# PLD_Local-Supply.net
KiCad netlist of a schematic drawn in Altium Designer
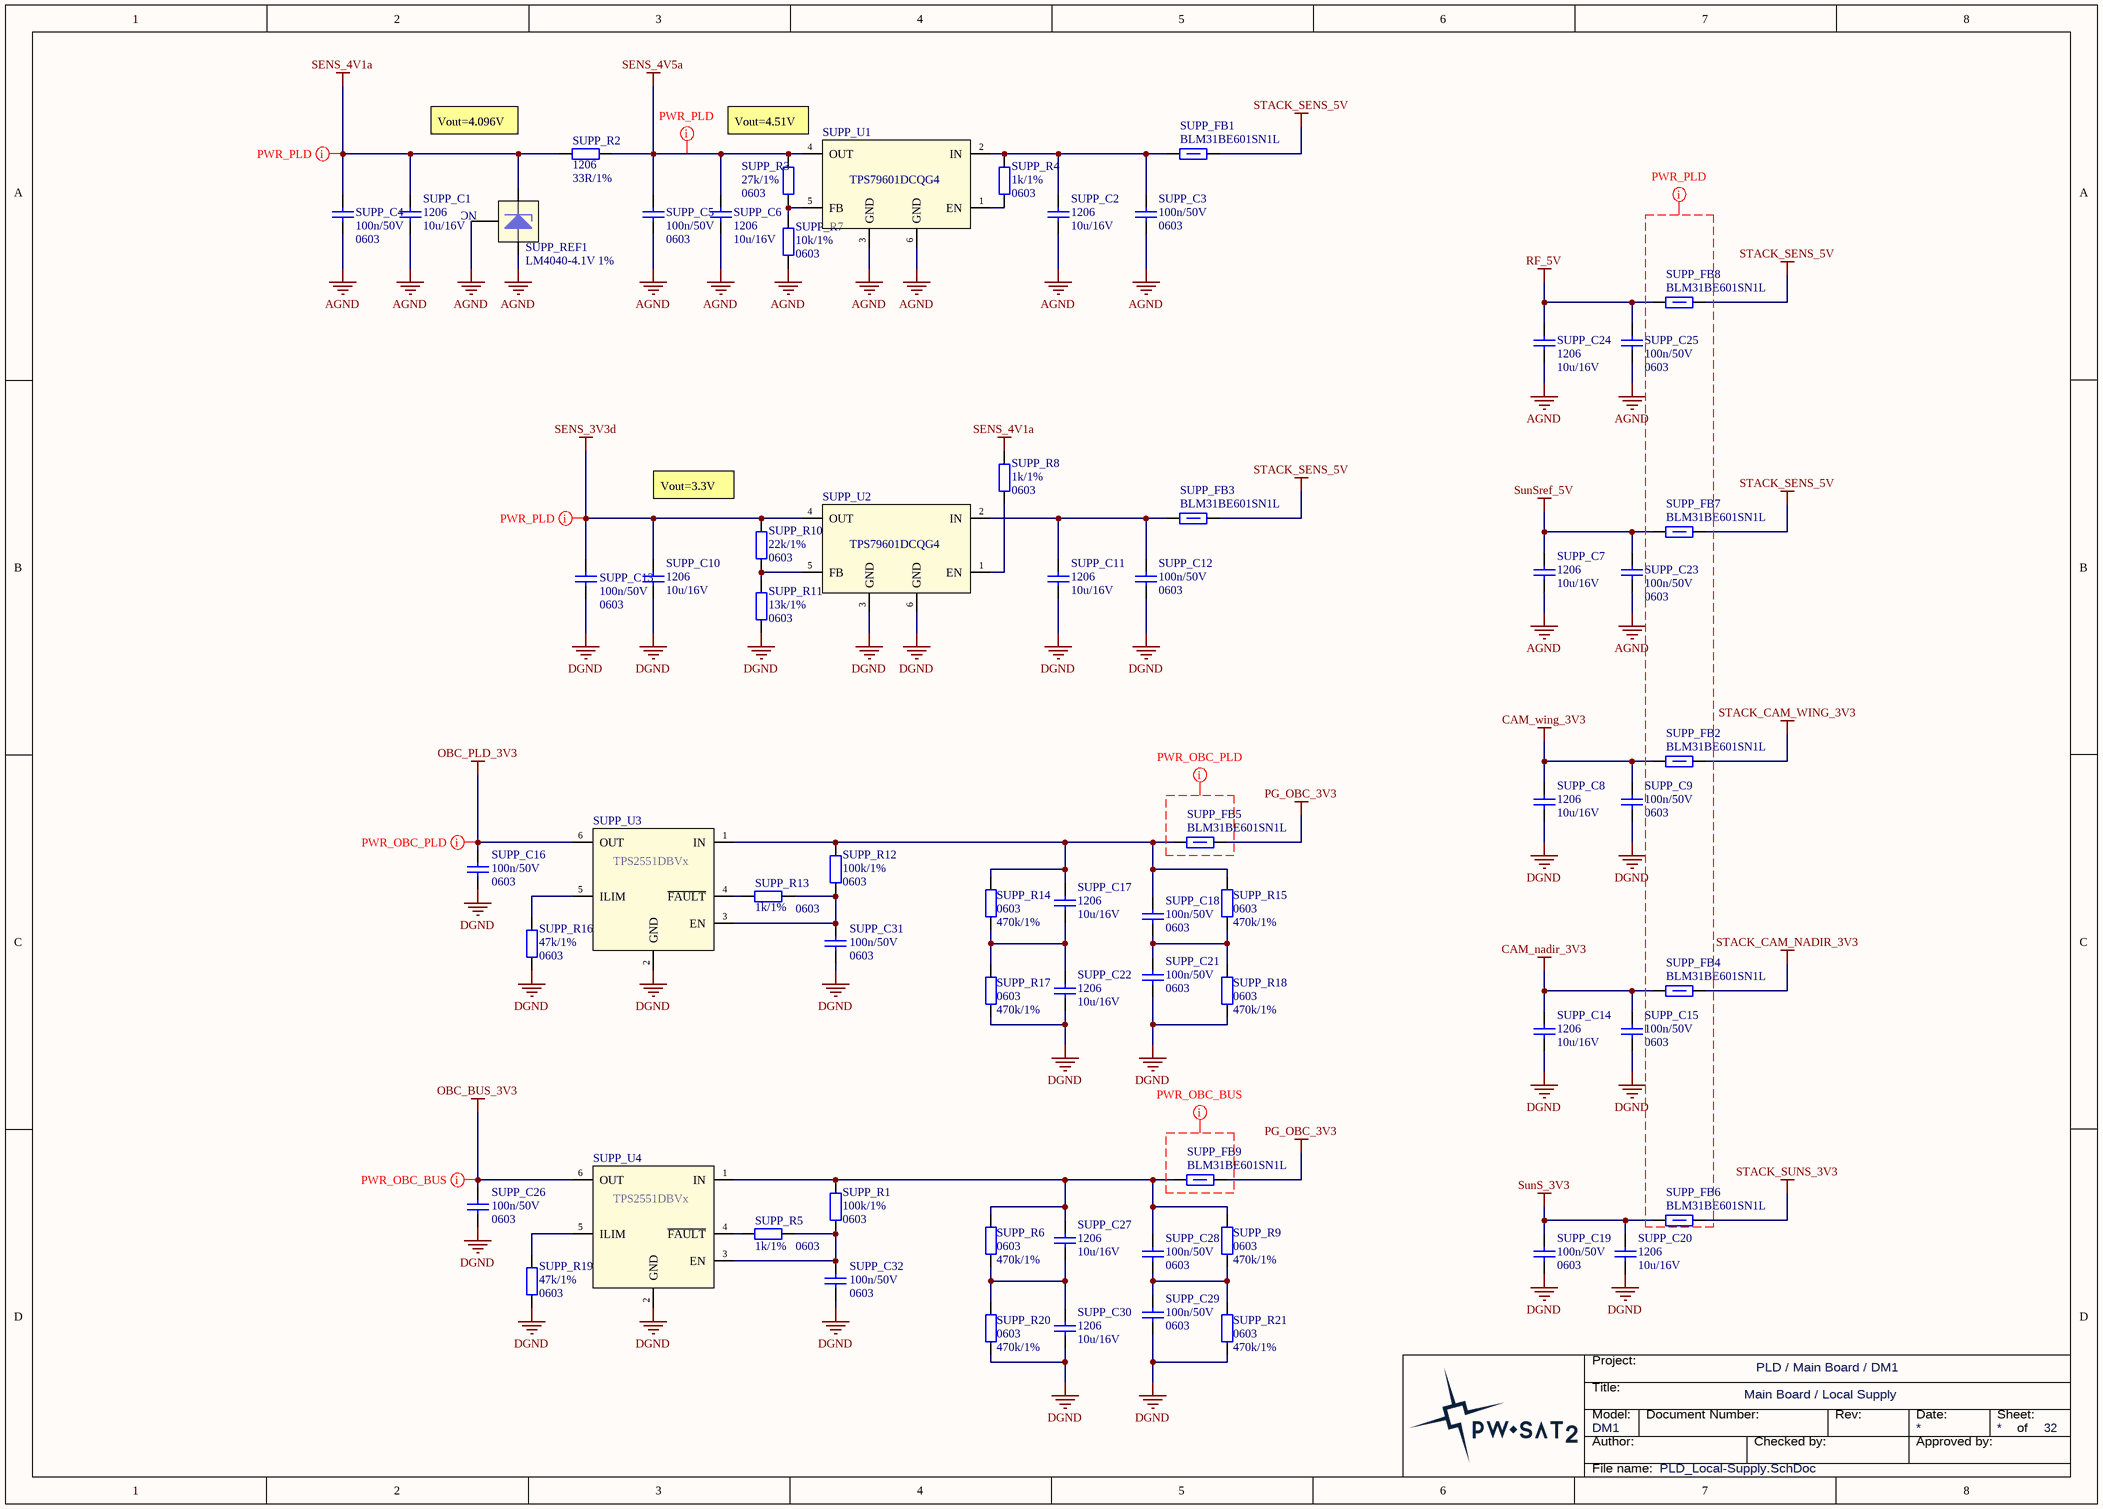
[diagram p0: PLD_Local-Supply.SchDoc]

(export (version "E")
  (design (tool "Eeschema 10.0.6"))
  (components
    (comp (ref "SUPP_C1")
      (value "10u/16V")
      (footprint "SMD_Capacitor_1206")
      (description "Ceramic Cap Kemet COTS 10u/16V X7R 1206")
      (fields
        (field (name "MANUFACTURERPARTNUMBER") "C1206T106K4RACTU")
        (field (name "MANUFACTURER") "Kemet")
        (field (name "PACKGE") "1206")
      )
      (libsource (lib "capacitors") (part "Cer_C1206T106K4RACTU"))
    )
    (comp (ref "SUPP_C2")
      (value "10u/16V")
      (footprint "SMD_Capacitor_1206")
      (description "Ceramic Cap Kemet COTS 10u/16V X7R 1206")
      (fields
        (field (name "MANUFACTURERPARTNUMBER") "C1206T106K4RACTU")
        (field (name "MANUFACTURER") "Kemet")
        (field (name "PACKGE") "1206")
      )
      (libsource (lib "capacitors") (part "Cer_C1206T106K4RACTU"))
    )
    (comp (ref "SUPP_C3")
      (value "100n/50V")
      (footprint "SMD_Capacitor_0603")
      (description "Ceramic Cap Kemet COTS 100n/50V X7R 0603")
      (fields
        (field (name "MANUFACTURER") "Kemet")
        (field (name "MANUFACTURERPARTNUMBER") "C0603T104K5RALTU")
        (field (name "PACKAGE") "0603")
      )
      (libsource (lib "capacitors") (part "Cer_C0603T104K5RALTU"))
    )
    (comp (ref "SUPP_C4")
      (value "100n/50V")
      (footprint "SMD_Capacitor_0603")
      (description "Ceramic Cap Kemet COTS 100n/50V X7R 0603")
      (fields
        (field (name "MANUFACTURER") "Kemet")
        (field (name "MANUFACTURERPARTNUMBER") "C0603T104K5RALTU")
        (field (name "PACKAGE") "0603")
      )
      (libsource (lib "capacitors") (part "Cer_C0603T104K5RALTU"))
    )
    (comp (ref "SUPP_C5")
      (value "100n/50V")
      (footprint "SMD_Capacitor_0603")
      (description "Ceramic Cap Kemet COTS 100n/50V X7R 0603")
      (fields
        (field (name "MANUFACTURER") "Kemet")
        (field (name "MANUFACTURERPARTNUMBER") "C0603T104K5RALTU")
        (field (name "PACKAGE") "0603")
      )
      (libsource (lib "capacitors") (part "Cer_C0603T104K5RALTU"))
    )
    (comp (ref "SUPP_C6")
      (value "10u/16V")
      (footprint "SMD_Capacitor_1206")
      (description "Ceramic Cap Kemet COTS 10u/16V X7R 1206")
      (fields
        (field (name "MANUFACTURERPARTNUMBER") "C1206T106K4RACTU")
        (field (name "MANUFACTURER") "Kemet")
        (field (name "PACKGE") "1206")
      )
      (libsource (lib "capacitors") (part "Cer_C1206T106K4RACTU"))
    )
    (comp (ref "SUPP_C7")
      (value "10u/16V")
      (footprint "SMD_Capacitor_1206")
      (description "Ceramic Cap Kemet COTS 10u/16V X7R 1206")
      (fields
        (field (name "MANUFACTURERPARTNUMBER") "C1206T106K4RACTU")
        (field (name "MANUFACTURER") "Kemet")
        (field (name "PACKGE") "1206")
      )
      (libsource (lib "capacitors") (part "Cer_C1206T106K4RACTU"))
    )
    (comp (ref "SUPP_C8")
      (value "10u/16V")
      (footprint "SMD_Capacitor_1206")
      (description "Ceramic Cap Kemet COTS 10u/16V X7R 1206")
      (fields
        (field (name "MANUFACTURERPARTNUMBER") "C1206T106K4RACTU")
        (field (name "MANUFACTURER") "Kemet")
        (field (name "PACKGE") "1206")
      )
      (libsource (lib "capacitors") (part "Cer_C1206T106K4RACTU"))
    )
    (comp (ref "SUPP_C9")
      (value "100n/50V")
      (footprint "SMD_Capacitor_0603")
      (description "Ceramic Cap Kemet COTS 100n/50V X7R 0603")
      (fields
        (field (name "MANUFACTURER") "Kemet")
        (field (name "MANUFACTURERPARTNUMBER") "C0603T104K5RALTU")
        (field (name "PACKAGE") "0603")
      )
      (libsource (lib "capacitors") (part "Cer_C0603T104K5RALTU"))
    )
    (comp (ref "SUPP_C10")
      (value "10u/16V")
      (footprint "SMD_Capacitor_1206")
      (description "Ceramic Cap Kemet COTS 10u/16V X7R 1206")
      (fields
        (field (name "MANUFACTURERPARTNUMBER") "C1206T106K4RACTU")
        (field (name "MANUFACTURER") "Kemet")
        (field (name "PACKGE") "1206")
      )
      (libsource (lib "capacitors") (part "Cer_C1206T106K4RACTU"))
    )
    (comp (ref "SUPP_C11")
      (value "10u/16V")
      (footprint "SMD_Capacitor_1206")
      (description "Ceramic Cap Kemet COTS 10u/16V X7R 1206")
      (fields
        (field (name "MANUFACTURERPARTNUMBER") "C1206T106K4RACTU")
        (field (name "MANUFACTURER") "Kemet")
        (field (name "PACKGE") "1206")
      )
      (libsource (lib "capacitors") (part "Cer_C1206T106K4RACTU"))
    )
    (comp (ref "SUPP_C12")
      (value "100n/50V")
      (footprint "SMD_Capacitor_0603")
      (description "Ceramic Cap Kemet COTS 100n/50V X7R 0603")
      (fields
        (field (name "MANUFACTURER") "Kemet")
        (field (name "MANUFACTURERPARTNUMBER") "C0603T104K5RALTU")
        (field (name "PACKAGE") "0603")
      )
      (libsource (lib "capacitors") (part "Cer_C0603T104K5RALTU"))
    )
    (comp (ref "SUPP_C13")
      (value "100n/50V")
      (footprint "SMD_Capacitor_0603")
      (description "Ceramic Cap Kemet COTS 100n/50V X7R 0603")
      (fields
        (field (name "MANUFACTURER") "Kemet")
        (field (name "MANUFACTURERPARTNUMBER") "C0603T104K5RALTU")
        (field (name "PACKAGE") "0603")
      )
      (libsource (lib "capacitors") (part "Cer_C0603T104K5RALTU"))
    )
    (comp (ref "SUPP_C14")
      (value "10u/16V")
      (footprint "SMD_Capacitor_1206")
      (description "Ceramic Cap Kemet COTS 10u/16V X7R 1206")
      (fields
        (field (name "MANUFACTURERPARTNUMBER") "C1206T106K4RACTU")
        (field (name "MANUFACTURER") "Kemet")
        (field (name "PACKGE") "1206")
      )
      (libsource (lib "capacitors") (part "Cer_C1206T106K4RACTU"))
    )
    (comp (ref "SUPP_C15")
      (value "100n/50V")
      (footprint "SMD_Capacitor_0603")
      (description "Ceramic Cap Kemet COTS 100n/50V X7R 0603")
      (fields
        (field (name "MANUFACTURER") "Kemet")
        (field (name "MANUFACTURERPARTNUMBER") "C0603T104K5RALTU")
        (field (name "PACKAGE") "0603")
      )
      (libsource (lib "capacitors") (part "Cer_C0603T104K5RALTU"))
    )
    (comp (ref "SUPP_C16")
      (value "100n/50V")
      (footprint "SMD_Capacitor_0603")
      (description "Ceramic Cap Kemet COTS 100n/50V X7R 0603")
      (fields
        (field (name "MANUFACTURER") "Kemet")
        (field (name "MANUFACTURERPARTNUMBER") "C0603T104K5RALTU")
        (field (name "PACKAGE") "0603")
      )
      (libsource (lib "capacitors") (part "Cer_C0603T104K5RALTU"))
    )
    (comp (ref "SUPP_C17")
      (value "10u/16V")
      (footprint "SMD_Capacitor_1206")
      (description "Ceramic Cap Kemet COTS 10u/16V X7R 1206")
      (fields
        (field (name "MANUFACTURERPARTNUMBER") "C1206T106K4RACTU")
        (field (name "MANUFACTURER") "Kemet")
        (field (name "PACKGE") "1206")
      )
      (libsource (lib "capacitors") (part "Cer_C1206T106K4RACTU"))
    )
    (comp (ref "SUPP_C18")
      (value "100n/50V")
      (footprint "SMD_Capacitor_0603")
      (description "Ceramic Cap Kemet COTS 100n/50V X7R 0603")
      (fields
        (field (name "MANUFACTURER") "Kemet")
        (field (name "MANUFACTURERPARTNUMBER") "C0603T104K5RALTU")
        (field (name "PACKAGE") "0603")
      )
      (libsource (lib "capacitors") (part "Cer_C0603T104K5RALTU"))
    )
    (comp (ref "SUPP_C19")
      (value "100n/50V")
      (footprint "SMD_Capacitor_0603")
      (description "Ceramic Cap Kemet COTS 100n/50V X7R 0603")
      (fields
        (field (name "MANUFACTURER") "Kemet")
        (field (name "MANUFACTURERPARTNUMBER") "C0603T104K5RALTU")
        (field (name "PACKAGE") "0603")
      )
      (libsource (lib "capacitors") (part "Cer_C0603T104K5RALTU"))
    )
    (comp (ref "SUPP_C20")
      (value "10u/16V")
      (footprint "SMD_Capacitor_1206")
      (description "Ceramic Cap Kemet COTS 10u/16V X7R 1206")
      (fields
        (field (name "MANUFACTURERPARTNUMBER") "C1206T106K4RACTU")
        (field (name "MANUFACTURER") "Kemet")
        (field (name "PACKGE") "1206")
      )
      (libsource (lib "capacitors") (part "Cer_C1206T106K4RACTU"))
    )
    (comp (ref "SUPP_C21")
      (value "100n/50V")
      (footprint "SMD_Capacitor_0603")
      (description "Ceramic Cap Kemet COTS 100n/50V X7R 0603")
      (fields
        (field (name "MANUFACTURER") "Kemet")
        (field (name "MANUFACTURERPARTNUMBER") "C0603T104K5RALTU")
        (field (name "PACKAGE") "0603")
      )
      (libsource (lib "capacitors") (part "Cer_C0603T104K5RALTU"))
    )
    (comp (ref "SUPP_C22")
      (value "10u/16V")
      (footprint "SMD_Capacitor_1206")
      (description "Ceramic Cap Kemet COTS 10u/16V X7R 1206")
      (fields
        (field (name "MANUFACTURERPARTNUMBER") "C1206T106K4RACTU")
        (field (name "MANUFACTURER") "Kemet")
        (field (name "PACKGE") "1206")
      )
      (libsource (lib "capacitors") (part "Cer_C1206T106K4RACTU"))
    )
    (comp (ref "SUPP_C23")
      (value "100n/50V")
      (footprint "SMD_Capacitor_0603")
      (description "Ceramic Cap Kemet COTS 100n/50V X7R 0603")
      (fields
        (field (name "MANUFACTURER") "Kemet")
        (field (name "MANUFACTURERPARTNUMBER") "C0603T104K5RALTU")
        (field (name "PACKAGE") "0603")
      )
      (libsource (lib "capacitors") (part "Cer_C0603T104K5RALTU"))
    )
    (comp (ref "SUPP_C24")
      (value "10u/16V")
      (footprint "SMD_Capacitor_1206")
      (description "Ceramic Cap Kemet COTS 10u/16V X7R 1206")
      (fields
        (field (name "MANUFACTURERPARTNUMBER") "C1206T106K4RACTU")
        (field (name "MANUFACTURER") "Kemet")
        (field (name "PACKGE") "1206")
      )
      (libsource (lib "capacitors") (part "Cer_C1206T106K4RACTU"))
    )
    (comp (ref "SUPP_C25")
      (value "100n/50V")
      (footprint "SMD_Capacitor_0603")
      (description "Ceramic Cap Kemet COTS 100n/50V X7R 0603")
      (fields
        (field (name "MANUFACTURER") "Kemet")
        (field (name "MANUFACTURERPARTNUMBER") "C0603T104K5RALTU")
        (field (name "PACKAGE") "0603")
      )
      (libsource (lib "capacitors") (part "Cer_C0603T104K5RALTU"))
    )
    (comp (ref "SUPP_C26")
      (value "100n/50V")
      (footprint "SMD_Capacitor_0603")
      (description "Ceramic Cap Kemet COTS 100n/50V X7R 0603")
      (fields
        (field (name "MANUFACTURER") "Kemet")
        (field (name "MANUFACTURERPARTNUMBER") "C0603T104K5RALTU")
        (field (name "PACKAGE") "0603")
      )
      (libsource (lib "capacitors") (part "Cer_C0603T104K5RALTU"))
    )
    (comp (ref "SUPP_C27")
      (value "10u/16V")
      (footprint "SMD_Capacitor_1206")
      (description "Ceramic Cap Kemet COTS 10u/16V X7R 1206")
      (fields
        (field (name "MANUFACTURERPARTNUMBER") "C1206T106K4RACTU")
        (field (name "MANUFACTURER") "Kemet")
        (field (name "PACKGE") "1206")
      )
      (libsource (lib "capacitors") (part "Cer_C1206T106K4RACTU"))
    )
    (comp (ref "SUPP_C28")
      (value "100n/50V")
      (footprint "SMD_Capacitor_0603")
      (description "Ceramic Cap Kemet COTS 100n/50V X7R 0603")
      (fields
        (field (name "MANUFACTURER") "Kemet")
        (field (name "MANUFACTURERPARTNUMBER") "C0603T104K5RALTU")
        (field (name "PACKAGE") "0603")
      )
      (libsource (lib "capacitors") (part "Cer_C0603T104K5RALTU"))
    )
    (comp (ref "SUPP_C29")
      (value "100n/50V")
      (footprint "SMD_Capacitor_0603")
      (description "Ceramic Cap Kemet COTS 100n/50V X7R 0603")
      (fields
        (field (name "MANUFACTURER") "Kemet")
        (field (name "MANUFACTURERPARTNUMBER") "C0603T104K5RALTU")
        (field (name "PACKAGE") "0603")
      )
      (libsource (lib "capacitors") (part "Cer_C0603T104K5RALTU"))
    )
    (comp (ref "SUPP_C30")
      (value "10u/16V")
      (footprint "SMD_Capacitor_1206")
      (description "Ceramic Cap Kemet COTS 10u/16V X7R 1206")
      (fields
        (field (name "MANUFACTURERPARTNUMBER") "C1206T106K4RACTU")
        (field (name "MANUFACTURER") "Kemet")
        (field (name "PACKGE") "1206")
      )
      (libsource (lib "capacitors") (part "Cer_C1206T106K4RACTU"))
    )
    (comp (ref "SUPP_C31")
      (value "100n/50V")
      (footprint "SMD_Capacitor_0603")
      (description "Ceramic Cap Kemet COTS 100n/50V X7R 0603")
      (fields
        (field (name "MANUFACTURER") "Kemet")
        (field (name "MANUFACTURERPARTNUMBER") "C0603T104K5RALTU")
        (field (name "PACKAGE") "0603")
      )
      (libsource (lib "capacitors") (part "Cer_C0603T104K5RALTU"))
    )
    (comp (ref "SUPP_C32")
      (value "100n/50V")
      (footprint "SMD_Capacitor_0603")
      (description "Ceramic Cap Kemet COTS 100n/50V X7R 0603")
      (fields
        (field (name "MANUFACTURER") "Kemet")
        (field (name "MANUFACTURERPARTNUMBER") "C0603T104K5RALTU")
        (field (name "PACKAGE") "0603")
      )
      (libsource (lib "capacitors") (part "Cer_C0603T104K5RALTU"))
    )
    (comp (ref "SUPP_FB1")
      (value "600R/100MHz")
      (footprint "1206")
      (description "Ferrite Bead")
      (fields (field (name "MANUFACTURER") "Murata") (field (name "MANUFACTURERPARTNUMBER") "BLM31BE601SN1L"))
      (libsource (lib "inductors") (part "FerriteBead"))
    )
    (comp (ref "SUPP_FB2")
      (value "600R/100MHz")
      (footprint "1206")
      (description "Ferrite Bead")
      (fields (field (name "MANUFACTURER") "Murata") (field (name "MANUFACTURERPARTNUMBER") "BLM31BE601SN1L"))
      (libsource (lib "inductors") (part "FerriteBead"))
    )
    (comp (ref "SUPP_FB3")
      (value "600R/100MHz")
      (footprint "1206")
      (description "Ferrite Bead")
      (fields (field (name "MANUFACTURER") "Murata") (field (name "MANUFACTURERPARTNUMBER") "BLM31BE601SN1L"))
      (libsource (lib "inductors") (part "FerriteBead"))
    )
    (comp (ref "SUPP_FB4")
      (value "600R/100MHz")
      (footprint "1206")
      (description "Ferrite Bead")
      (fields (field (name "MANUFACTURER") "Murata") (field (name "MANUFACTURERPARTNUMBER") "BLM31BE601SN1L"))
      (libsource (lib "inductors") (part "FerriteBead"))
    )
    (comp (ref "SUPP_FB5")
      (value "600R/100MHz")
      (footprint "1206")
      (description "Ferrite Bead")
      (fields (field (name "MANUFACTURER") "Murata") (field (name "MANUFACTURERPARTNUMBER") "BLM31BE601SN1L"))
      (libsource (lib "inductors") (part "FerriteBead"))
    )
    (comp (ref "SUPP_FB6")
      (value "600R/100MHz")
      (footprint "1206")
      (description "Ferrite Bead")
      (fields (field (name "MANUFACTURER") "Murata") (field (name "MANUFACTURERPARTNUMBER") "BLM31BE601SN1L"))
      (libsource (lib "inductors") (part "FerriteBead"))
    )
    (comp (ref "SUPP_FB7")
      (value "600R/100MHz")
      (footprint "1206")
      (description "Ferrite Bead")
      (fields (field (name "MANUFACTURER") "Murata") (field (name "MANUFACTURERPARTNUMBER") "BLM31BE601SN1L"))
      (libsource (lib "inductors") (part "FerriteBead"))
    )
    (comp (ref "SUPP_FB8")
      (value "600R/100MHz")
      (footprint "1206")
      (description "Ferrite Bead")
      (fields (field (name "MANUFACTURER") "Murata") (field (name "MANUFACTURERPARTNUMBER") "BLM31BE601SN1L"))
      (libsource (lib "inductors") (part "FerriteBead"))
    )
    (comp (ref "SUPP_FB9")
      (value "600R/100MHz")
      (footprint "1206")
      (description "Ferrite Bead")
      (fields (field (name "MANUFACTURER") "Murata") (field (name "MANUFACTURERPARTNUMBER") "BLM31BE601SN1L"))
      (libsource (lib "inductors") (part "FerriteBead"))
    )
    (comp (ref "SUPP_R1")
      (value "100k/1%")
      (footprint "SMD_Resistor_0603")
      (description "100k/1% Vishay CRCW 0603 Resistor. 100mW, 100ppm, 75V.")
      (fields
        (field (name "MANUFACTURER") "Vishay")
        (field (name "MANUFACTURERPARTNUMBER") "CRCW0603100KFKxxxx")
        (field (name "PACKAGE") "0603")
      )
      (libsource (lib "resistors") (part "CRCW0603100KFKxxxx"))
    )
    (comp (ref "SUPP_R2")
      (value "33R/1%")
      (footprint "SMD_Resistor_1206")
      (description "33R/1% Vishay CRCW 1206 Resistor. 250mW, 100ppm, 200V.")
      (fields
        (field (name "MANUFACTURERPARTNUMBER") "CRCW120633R0FKxxxx")
        (field (name "MANUFACTURER") "Vishay")
        (field (name "PACKAGE") "1206")
      )
      (libsource (lib "resistors") (part "CRCW120633R0FKxxxx"))
    )
    (comp (ref "SUPP_R3")
      (value "27k/1%")
      (footprint "SMD_Resistor_0603")
      (fields (field (name "PACKAGE") "0603"))
      (libsource (lib "resistors") (part "Res"))
    )
    (comp (ref "SUPP_R4")
      (value "1k/1%")
      (footprint "SMD_Resistor_0603")
      (description "1k/1% Vishay CRCW 0603 Resistor. 100mW, 100ppm, 75V.")
      (fields
        (field (name "MANUFACTURER") "Vishay")
        (field (name "MANUFACTURERPARTNUMBER") "CRCW06031K00FKxxxx")
        (field (name "PACKAGE") "0603")
      )
      (libsource (lib "") (part "CRCW06031K00FKxxxx_1"))
    )
    (comp (ref "SUPP_R5")
      (value "1k/1%")
      (footprint "SMD_Resistor_0603")
      (description "1k/1% Vishay CRCW 0603 Resistor. 100mW, 100ppm, 75V.")
      (fields
        (field (name "MANUFACTURER") "Vishay")
        (field (name "MANUFACTURERPARTNUMBER") "CRCW06031K00FKxxxx")
        (field (name "PACKAGE") "0603")
      )
      (libsource (lib "resistors") (part "CRCW06031K00FKxxxx"))
    )
    (comp (ref "SUPP_R6")
      (value "470k/1%")
      (footprint "SMD_Resistor_0603")
      (description "470k/1% Vishay CRCW 0603 Resistor. 100mW, 100ppm, 75V.")
      (fields
        (field (name "MANUFACTURER") "Vishay")
        (field (name "MANUFACTURERPARTNUMBER") "CRCW0603470KFKxxxx")
        (field (name "PACKAGE") "0603")
      )
      (libsource (lib "") (part "CRCW0603470KFKxxxx_1"))
    )
    (comp (ref "SUPP_R7")
      (value "10k/1%")
      (footprint "SMD_Resistor_0603")
      (description "10k/1% Vishay CRCW 0603 Resistor. 100mW, 100ppm, 75V.")
      (fields
        (field (name "MANUFACTURER") "Vishay")
        (field (name "MANUFACTURERPARTNUMBER") "CRCW060310K0FKxxxx")
        (field (name "PACKAGE") "0603")
      )
      (libsource (lib "resistors") (part "CRCW060310K0FKxxxx"))
    )
    (comp (ref "SUPP_R8")
      (value "1k/1%")
      (footprint "SMD_Resistor_0603")
      (description "1k/1% Vishay CRCW 0603 Resistor. 100mW, 100ppm, 75V.")
      (fields
        (field (name "MANUFACTURER") "Vishay")
        (field (name "MANUFACTURERPARTNUMBER") "CRCW06031K00FKxxxx")
        (field (name "PACKAGE") "0603")
      )
      (libsource (lib "") (part "CRCW06031K00FKxxxx_1"))
    )
    (comp (ref "SUPP_R9")
      (value "470k/1%")
      (footprint "SMD_Resistor_0603")
      (description "470k/1% Vishay CRCW 0603 Resistor. 100mW, 100ppm, 75V.")
      (fields
        (field (name "MANUFACTURER") "Vishay")
        (field (name "MANUFACTURERPARTNUMBER") "CRCW0603470KFKxxxx")
        (field (name "PACKAGE") "0603")
      )
      (libsource (lib "resistors") (part "CRCW0603470KFKxxxx"))
    )
    (comp (ref "SUPP_R10")
      (value "22k/1%")
      (footprint "SMD_Resistor_0603")
      (fields (field (name "PACKAGE") "0603"))
      (libsource (lib "resistors") (part "Res"))
    )
    (comp (ref "SUPP_R11")
      (value "13k/1%")
      (footprint "SMD_Resistor_0603")
      (fields (field (name "PACKAGE") "0603"))
      (libsource (lib "resistors") (part "Res"))
    )
    (comp (ref "SUPP_R12")
      (value "100k/1%")
      (footprint "SMD_Resistor_0603")
      (description "100k/1% Vishay CRCW 0603 Resistor. 100mW, 100ppm, 75V.")
      (fields
        (field (name "MANUFACTURER") "Vishay")
        (field (name "MANUFACTURERPARTNUMBER") "CRCW0603100KFKxxxx")
        (field (name "PACKAGE") "0603")
      )
      (libsource (lib "resistors") (part "CRCW0603100KFKxxxx"))
    )
    (comp (ref "SUPP_R13")
      (value "1k/1%")
      (footprint "SMD_Resistor_0603")
      (description "1k/1% Vishay CRCW 0603 Resistor. 100mW, 100ppm, 75V.")
      (fields
        (field (name "MANUFACTURER") "Vishay")
        (field (name "MANUFACTURERPARTNUMBER") "CRCW06031K00FKxxxx")
        (field (name "PACKAGE") "0603")
      )
      (libsource (lib "resistors") (part "CRCW06031K00FKxxxx"))
    )
    (comp (ref "SUPP_R14")
      (value "470k/1%")
      (footprint "SMD_Resistor_0603")
      (description "470k/1% Vishay CRCW 0603 Resistor. 100mW, 100ppm, 75V.")
      (fields
        (field (name "MANUFACTURER") "Vishay")
        (field (name "MANUFACTURERPARTNUMBER") "CRCW0603470KFKxxxx")
        (field (name "PACKAGE") "0603")
      )
      (libsource (lib "") (part "CRCW0603470KFKxxxx_1"))
    )
    (comp (ref "SUPP_R15")
      (value "470k/1%")
      (footprint "SMD_Resistor_0603")
      (description "470k/1% Vishay CRCW 0603 Resistor. 100mW, 100ppm, 75V.")
      (fields
        (field (name "MANUFACTURER") "Vishay")
        (field (name "MANUFACTURERPARTNUMBER") "CRCW0603470KFKxxxx")
        (field (name "PACKAGE") "0603")
      )
      (libsource (lib "resistors") (part "CRCW0603470KFKxxxx"))
    )
    (comp (ref "SUPP_R16")
      (value "47k/1%")
      (footprint "SMD_Resistor_0603")
      (description "47k/1% Vishay CRCW 0603 Resistor. 100mW, 100ppm, 75V.")
      (fields
        (field (name "MANUFACTURER") "Vishay")
        (field (name "MANUFACTURERPARTNUMBER") "CRCW060347K0FKxxxx")
        (field (name "PACKAGE") "0603")
      )
      (libsource (lib "resistors") (part "CRCW060347K0FKxxxx"))
    )
    (comp (ref "SUPP_R17")
      (value "470k/1%")
      (footprint "SMD_Resistor_0603")
      (description "470k/1% Vishay CRCW 0603 Resistor. 100mW, 100ppm, 75V.")
      (fields
        (field (name "MANUFACTURER") "Vishay")
        (field (name "MANUFACTURERPARTNUMBER") "CRCW0603470KFKxxxx")
        (field (name "PACKAGE") "0603")
      )
      (libsource (lib "") (part "CRCW0603470KFKxxxx_1"))
    )
    (comp (ref "SUPP_R18")
      (value "470k/1%")
      (footprint "SMD_Resistor_0603")
      (description "470k/1% Vishay CRCW 0603 Resistor. 100mW, 100ppm, 75V.")
      (fields
        (field (name "MANUFACTURER") "Vishay")
        (field (name "MANUFACTURERPARTNUMBER") "CRCW0603470KFKxxxx")
        (field (name "PACKAGE") "0603")
      )
      (libsource (lib "resistors") (part "CRCW0603470KFKxxxx"))
    )
    (comp (ref "SUPP_R19")
      (value "47k/1%")
      (footprint "SMD_Resistor_0603")
      (description "47k/1% Vishay CRCW 0603 Resistor. 100mW, 100ppm, 75V.")
      (fields
        (field (name "MANUFACTURER") "Vishay")
        (field (name "MANUFACTURERPARTNUMBER") "CRCW060347K0FKxxxx")
        (field (name "PACKAGE") "0603")
      )
      (libsource (lib "resistors") (part "CRCW060347K0FKxxxx"))
    )
    (comp (ref "SUPP_R20")
      (value "470k/1%")
      (footprint "SMD_Resistor_0603")
      (description "470k/1% Vishay CRCW 0603 Resistor. 100mW, 100ppm, 75V.")
      (fields
        (field (name "MANUFACTURER") "Vishay")
        (field (name "MANUFACTURERPARTNUMBER") "CRCW0603470KFKxxxx")
        (field (name "PACKAGE") "0603")
      )
      (libsource (lib "") (part "CRCW0603470KFKxxxx_1"))
    )
    (comp (ref "SUPP_R21")
      (value "470k/1%")
      (footprint "SMD_Resistor_0603")
      (description "470k/1% Vishay CRCW 0603 Resistor. 100mW, 100ppm, 75V.")
      (fields
        (field (name "MANUFACTURER") "Vishay")
        (field (name "MANUFACTURERPARTNUMBER") "CRCW0603470KFKxxxx")
        (field (name "PACKAGE") "0603")
      )
      (libsource (lib "resistors") (part "CRCW0603470KFKxxxx"))
    )
    (comp (ref "SUPP_REF1")
      (value "LM4040-4.1V 1%")
      (footprint "SOT23-3")
      (description "Shunt V-REF, 4.096V, 1%, SOT23-3")
      (fields
        (field (name "MANUFACTURERPARTNUMBER") "LM4040CIM3-4.1")
        (field (name "MANUFACTURER") "Texas Instruments")
      )
      (libsource (lib "diodes") (part "LM4040CIM3-4.1"))
    )
    (comp (ref "SUPP_U1")
      (value "~")
      (footprint "TI-DCQ")
      (description "1A, Ajdustable LDO, Ultralow-Noise, High PSRR, Fast, RF")
      (fields
        (field (name "MANUFACTURER") "Texas Instruments")
        (field (name "MANUFACTURERPARTNUMBER") "TPS79601DCQG4")
      )
      (libsource (lib "microcircuits") (part "TPS79601DCQG4"))
    )
    (comp (ref "SUPP_U2")
      (value "~")
      (footprint "TI-DCQ")
      (description "1A, Ajdustable LDO, Ultralow-Noise, High PSRR, Fast, RF")
      (fields
        (field (name "MANUFACTURER") "Texas Instruments")
        (field (name "MANUFACTURERPARTNUMBER") "TPS79601DCQG4")
      )
      (libsource (lib "microcircuits") (part "TPS79601DCQG4"))
    )
    (comp (ref "SUPP_U3")
      (value "TPS2551DBVx")
      (footprint "SOT23-6")
      (description "Adjustable Current-Limited Power-Distribution Switch.")
      (fields (field (name "MANUFACTURER") "Texas Instruments"))
      (libsource (lib "microcircuits") (part "TPS2551DBVx"))
    )
    (comp (ref "SUPP_U4")
      (value "TPS2551DBVx")
      (footprint "SOT23-6")
      (description "Adjustable Current-Limited Power-Distribution Switch.")
      (fields (field (name "MANUFACTURER") "Texas Instruments"))
      (libsource (lib "microcircuits") (part "TPS2551DBVx"))
    )
  )
  (nets
    (net (code "1") (name "AGND") (class "Default")
      (node (ref "SUPP_C1") (pin "2") (pinfunction "2_2") (pintype "passive"))
      (node (ref "SUPP_C2") (pin "2") (pinfunction "2_2") (pintype "passive"))
      (node (ref "SUPP_C23") (pin "1") (pinfunction "1_1") (pintype "passive"))
      (node (ref "SUPP_C24") (pin "2") (pinfunction "2_2") (pintype "passive"))
      (node (ref "SUPP_C25") (pin "1") (pinfunction "1_1") (pintype "passive"))
      (node (ref "SUPP_C3") (pin "2") (pinfunction "2_2") (pintype "passive"))
      (node (ref "SUPP_C4") (pin "2") (pinfunction "2_2") (pintype "passive"))
      (node (ref "SUPP_C5") (pin "2") (pinfunction "2_2") (pintype "passive"))
      (node (ref "SUPP_C6") (pin "2") (pinfunction "2_2") (pintype "passive"))
      (node (ref "SUPP_C7") (pin "2") (pinfunction "2_2") (pintype "passive"))
      (node (ref "SUPP_R7") (pin "2") (pinfunction "2_2") (pintype "passive"))
      (node (ref "SUPP_REF1") (pin "2") (pinfunction "A_2") (pintype "passive"))
      (node (ref "SUPP_REF1") (pin "3") (pinfunction "NC_3") (pintype "passive"))
      (node (ref "SUPP_U1") (pin "3") (pinfunction "GND_3") (pintype "passive"))
      (node (ref "SUPP_U1") (pin "6") (pinfunction "GND_6") (pintype "passive"))
    )
    (net (code "2") (name "CAM_nadir_3V3") (class "Default")
      (node (ref "SUPP_C14") (pin "1") (pinfunction "1_1") (pintype "passive"))
      (node (ref "SUPP_C15") (pin "1") (pinfunction "1_1") (pintype "passive"))
      (node (ref "SUPP_FB4") (pin "2") (pinfunction "2_2") (pintype "passive"))
    )
    (net (code "3") (name "CAM_wing_3V3") (class "Default")
      (node (ref "SUPP_C8") (pin "1") (pinfunction "1_1") (pintype "passive"))
      (node (ref "SUPP_C9") (pin "1") (pinfunction "1_1") (pintype "passive"))
      (node (ref "SUPP_FB2") (pin "2") (pinfunction "2_2") (pintype "passive"))
    )
    (net (code "4") (name "DGND") (class "Default")
      (node (ref "SUPP_C10") (pin "2") (pinfunction "2_2") (pintype "passive"))
      (node (ref "SUPP_C11") (pin "2") (pinfunction "2_2") (pintype "passive"))
      (node (ref "SUPP_C12") (pin "2") (pinfunction "2_2") (pintype "passive"))
      (node (ref "SUPP_C13") (pin "2") (pinfunction "2_2") (pintype "passive"))
      (node (ref "SUPP_C14") (pin "2") (pinfunction "2_2") (pintype "passive"))
      (node (ref "SUPP_C15") (pin "2") (pinfunction "2_2") (pintype "passive"))
      (node (ref "SUPP_C16") (pin "1") (pinfunction "1_1") (pintype "passive"))
      (node (ref "SUPP_C19") (pin "2") (pinfunction "2_2") (pintype "passive"))
      (node (ref "SUPP_C20") (pin "2") (pinfunction "2_2") (pintype "passive"))
      (node (ref "SUPP_C21") (pin "2") (pinfunction "2_2") (pintype "passive"))
      (node (ref "SUPP_C22") (pin "2") (pinfunction "2_2") (pintype "passive"))
      (node (ref "SUPP_C26") (pin "1") (pinfunction "1_1") (pintype "passive"))
      (node (ref "SUPP_C29") (pin "2") (pinfunction "2_2") (pintype "passive"))
      (node (ref "SUPP_C30") (pin "2") (pinfunction "2_2") (pintype "passive"))
      (node (ref "SUPP_C31") (pin "1") (pinfunction "1_1") (pintype "passive"))
      (node (ref "SUPP_C32") (pin "1") (pinfunction "1_1") (pintype "passive"))
      (node (ref "SUPP_C8") (pin "2") (pinfunction "2_2") (pintype "passive"))
      (node (ref "SUPP_C9") (pin "2") (pinfunction "2_2") (pintype "passive"))
      (node (ref "SUPP_R11") (pin "2") (pinfunction "2_2") (pintype "passive"))
      (node (ref "SUPP_R16") (pin "2") (pinfunction "2_2") (pintype "passive"))
      (node (ref "SUPP_R17") (pin "2") (pinfunction "2_2") (pintype "passive"))
      (node (ref "SUPP_R18") (pin "2") (pinfunction "2_2") (pintype "passive"))
      (node (ref "SUPP_R19") (pin "2") (pinfunction "2_2") (pintype "passive"))
      (node (ref "SUPP_R20") (pin "2") (pinfunction "2_2") (pintype "passive"))
      (node (ref "SUPP_R21") (pin "2") (pinfunction "2_2") (pintype "passive"))
      (node (ref "SUPP_U2") (pin "3") (pinfunction "GND_3") (pintype "passive"))
      (node (ref "SUPP_U2") (pin "6") (pinfunction "GND_6") (pintype "passive"))
      (node (ref "SUPP_U3") (pin "2") (pinfunction "GND_2") (pintype "passive"))
      (node (ref "SUPP_U4") (pin "2") (pinfunction "GND_2") (pintype "passive"))
    )
    (net (code "5") (name "Net-(SUPP_C17-Pad2)") (class "Default")
      (node (ref "SUPP_C17") (pin "2") (pinfunction "2_2") (pintype "passive"))
      (node (ref "SUPP_C22") (pin "1") (pinfunction "1_1") (pintype "passive"))
      (node (ref "SUPP_R14") (pin "2") (pinfunction "2_2") (pintype "passive"))
      (node (ref "SUPP_R17") (pin "1") (pinfunction "1_1") (pintype "passive"))
    )
    (net (code "6") (name "Net-(SUPP_C18-Pad2)") (class "Default")
      (node (ref "SUPP_C18") (pin "2") (pinfunction "2_2") (pintype "passive"))
      (node (ref "SUPP_C21") (pin "1") (pinfunction "1_1") (pintype "passive"))
      (node (ref "SUPP_R15") (pin "2") (pinfunction "2_2") (pintype "passive"))
      (node (ref "SUPP_R18") (pin "1") (pinfunction "1_1") (pintype "passive"))
    )
    (net (code "7") (name "Net-(SUPP_C27-Pad2)") (class "Default")
      (node (ref "SUPP_C27") (pin "2") (pinfunction "2_2") (pintype "passive"))
      (node (ref "SUPP_C30") (pin "1") (pinfunction "1_1") (pintype "passive"))
      (node (ref "SUPP_R20") (pin "1") (pinfunction "1_1") (pintype "passive"))
      (node (ref "SUPP_R6") (pin "2") (pinfunction "2_2") (pintype "passive"))
    )
    (net (code "8") (name "Net-(SUPP_C28-Pad2)") (class "Default")
      (node (ref "SUPP_C28") (pin "2") (pinfunction "2_2") (pintype "passive"))
      (node (ref "SUPP_C29") (pin "1") (pinfunction "1_1") (pintype "passive"))
      (node (ref "SUPP_R21") (pin "1") (pinfunction "1_1") (pintype "passive"))
      (node (ref "SUPP_R9") (pin "2") (pinfunction "2_2") (pintype "passive"))
    )
    (net (code "9") (name "Net-(SUPP_U1-EN)") (class "Default")
      (node (ref "SUPP_R4") (pin "2") (pinfunction "2_2") (pintype "passive"))
      (node (ref "SUPP_U1") (pin "1") (pinfunction "EN_1") (pintype "passive"))
    )
    (net (code "10") (name "Net-(SUPP_U1-FB)") (class "Default")
      (node (ref "SUPP_R3") (pin "2") (pinfunction "2_2") (pintype "passive"))
      (node (ref "SUPP_R7") (pin "1") (pinfunction "1_1") (pintype "passive"))
      (node (ref "SUPP_U1") (pin "5") (pinfunction "FB_5") (pintype "passive"))
    )
    (net (code "11") (name "Net-(SUPP_U1-IN)") (class "Default")
      (node (ref "SUPP_C2") (pin "1") (pinfunction "1_1") (pintype "passive"))
      (node (ref "SUPP_C3") (pin "1") (pinfunction "1_1") (pintype "passive"))
      (node (ref "SUPP_FB1") (pin "2") (pinfunction "2_2") (pintype "passive"))
      (node (ref "SUPP_R4") (pin "1") (pinfunction "1_1") (pintype "passive"))
      (node (ref "SUPP_U1") (pin "2") (pinfunction "IN_2") (pintype "passive"))
    )
    (net (code "12") (name "Net-(SUPP_U2-EN)") (class "Default")
      (node (ref "SUPP_R8") (pin "2") (pinfunction "2_2") (pintype "passive"))
      (node (ref "SUPP_U2") (pin "1") (pinfunction "EN_1") (pintype "passive"))
    )
    (net (code "13") (name "Net-(SUPP_U2-FB)") (class "Default")
      (node (ref "SUPP_R10") (pin "2") (pinfunction "2_2") (pintype "passive"))
      (node (ref "SUPP_R11") (pin "1") (pinfunction "1_1") (pintype "passive"))
      (node (ref "SUPP_U2") (pin "5") (pinfunction "FB_5") (pintype "passive"))
    )
    (net (code "14") (name "Net-(SUPP_U2-IN)") (class "Default")
      (node (ref "SUPP_C11") (pin "1") (pinfunction "1_1") (pintype "passive"))
      (node (ref "SUPP_C12") (pin "1") (pinfunction "1_1") (pintype "passive"))
      (node (ref "SUPP_FB3") (pin "2") (pinfunction "2_2") (pintype "passive"))
      (node (ref "SUPP_U2") (pin "2") (pinfunction "IN_2") (pintype "passive"))
    )
    (net (code "15") (name "Net-(SUPP_U3-EN)") (class "Default")
      (node (ref "SUPP_C31") (pin "2") (pinfunction "2_2") (pintype "passive"))
      (node (ref "SUPP_R12") (pin "2") (pinfunction "2_2") (pintype "passive"))
      (node (ref "SUPP_R13") (pin "2") (pinfunction "2_2") (pintype "passive"))
      (node (ref "SUPP_U3") (pin "3") (pinfunction "EN_3") (pintype "passive"))
    )
    (net (code "16") (name "Net-(SUPP_U3-ILIM)") (class "Default")
      (node (ref "SUPP_R16") (pin "1") (pinfunction "1_1") (pintype "passive"))
      (node (ref "SUPP_U3") (pin "5") (pinfunction "ILIM_5") (pintype "passive"))
    )
    (net (code "17") (name "Net-(SUPP_U3-IN)") (class "Default")
      (node (ref "SUPP_C17") (pin "1") (pinfunction "1_1") (pintype "passive"))
      (node (ref "SUPP_C18") (pin "1") (pinfunction "1_1") (pintype "passive"))
      (node (ref "SUPP_FB5") (pin "2") (pinfunction "2_2") (pintype "passive"))
      (node (ref "SUPP_R12") (pin "1") (pinfunction "1_1") (pintype "passive"))
      (node (ref "SUPP_R14") (pin "1") (pinfunction "1_1") (pintype "passive"))
      (node (ref "SUPP_R15") (pin "1") (pinfunction "1_1") (pintype "passive"))
      (node (ref "SUPP_U3") (pin "1") (pinfunction "IN_1") (pintype "passive"))
    )
    (net (code "18") (name "Net-(SUPP_U3-~{FAULT})") (class "Default")
      (node (ref "SUPP_R13") (pin "1") (pinfunction "1_1") (pintype "passive"))
      (node (ref "SUPP_U3") (pin "4") (pinfunction "~{FAULT}_4") (pintype "passive"))
    )
    (net (code "19") (name "Net-(SUPP_U4-EN)") (class "Default")
      (node (ref "SUPP_C32") (pin "2") (pinfunction "2_2") (pintype "passive"))
      (node (ref "SUPP_R1") (pin "2") (pinfunction "2_2") (pintype "passive"))
      (node (ref "SUPP_R5") (pin "2") (pinfunction "2_2") (pintype "passive"))
      (node (ref "SUPP_U4") (pin "3") (pinfunction "EN_3") (pintype "passive"))
    )
    (net (code "20") (name "Net-(SUPP_U4-ILIM)") (class "Default")
      (node (ref "SUPP_R19") (pin "1") (pinfunction "1_1") (pintype "passive"))
      (node (ref "SUPP_U4") (pin "5") (pinfunction "ILIM_5") (pintype "passive"))
    )
    (net (code "21") (name "Net-(SUPP_U4-IN)") (class "Default")
      (node (ref "SUPP_C27") (pin "1") (pinfunction "1_1") (pintype "passive"))
      (node (ref "SUPP_C28") (pin "1") (pinfunction "1_1") (pintype "passive"))
      (node (ref "SUPP_FB9") (pin "2") (pinfunction "2_2") (pintype "passive"))
      (node (ref "SUPP_R1") (pin "1") (pinfunction "1_1") (pintype "passive"))
      (node (ref "SUPP_R6") (pin "1") (pinfunction "1_1") (pintype "passive"))
      (node (ref "SUPP_R9") (pin "1") (pinfunction "1_1") (pintype "passive"))
      (node (ref "SUPP_U4") (pin "1") (pinfunction "IN_1") (pintype "passive"))
    )
    (net (code "22") (name "Net-(SUPP_U4-~{FAULT})") (class "Default")
      (node (ref "SUPP_R5") (pin "1") (pinfunction "1_1") (pintype "passive"))
      (node (ref "SUPP_U4") (pin "4") (pinfunction "~{FAULT}_4") (pintype "passive"))
    )
    (net (code "23") (name "OBC_BUS_3V3") (class "Default")
      (node (ref "SUPP_C26") (pin "2") (pinfunction "2_2") (pintype "passive"))
      (node (ref "SUPP_U4") (pin "6") (pinfunction "OUT_6") (pintype "passive"))
    )
    (net (code "24") (name "OBC_PLD_3V3") (class "Default")
      (node (ref "SUPP_C16") (pin "2") (pinfunction "2_2") (pintype "passive"))
      (node (ref "SUPP_U3") (pin "6") (pinfunction "OUT_6") (pintype "passive"))
    )
    (net (code "25") (name "PG_OBC_3V3") (class "Default")
      (node (ref "SUPP_FB5") (pin "1") (pinfunction "1_1") (pintype "passive"))
      (node (ref "SUPP_FB9") (pin "1") (pinfunction "1_1") (pintype "passive"))
    )
    (net (code "26") (name "RF_5V") (class "Default")
      (node (ref "SUPP_C24") (pin "1") (pinfunction "1_1") (pintype "passive"))
      (node (ref "SUPP_C25") (pin "2") (pinfunction "2_2") (pintype "passive"))
      (node (ref "SUPP_FB8") (pin "2") (pinfunction "2_2") (pintype "passive"))
    )
    (net (code "27") (name "SENS_3V3d") (class "Default")
      (node (ref "SUPP_C10") (pin "1") (pinfunction "1_1") (pintype "passive"))
      (node (ref "SUPP_C13") (pin "1") (pinfunction "1_1") (pintype "passive"))
      (node (ref "SUPP_R10") (pin "1") (pinfunction "1_1") (pintype "passive"))
      (node (ref "SUPP_U2") (pin "4") (pinfunction "OUT_4") (pintype "passive"))
    )
    (net (code "28") (name "SENS_4V1a") (class "Default")
      (node (ref "SUPP_C1") (pin "1") (pinfunction "1_1") (pintype "passive"))
      (node (ref "SUPP_C4") (pin "1") (pinfunction "1_1") (pintype "passive"))
      (node (ref "SUPP_R2") (pin "1") (pinfunction "1_1") (pintype "passive"))
      (node (ref "SUPP_R8") (pin "1") (pinfunction "1_1") (pintype "passive"))
      (node (ref "SUPP_REF1") (pin "1") (pinfunction "K_1") (pintype "passive"))
    )
    (net (code "29") (name "SENS_4V5a") (class "Default")
      (node (ref "SUPP_C5") (pin "1") (pinfunction "1_1") (pintype "passive"))
      (node (ref "SUPP_C6") (pin "1") (pinfunction "1_1") (pintype "passive"))
      (node (ref "SUPP_R2") (pin "2") (pinfunction "2_2") (pintype "passive"))
      (node (ref "SUPP_R3") (pin "1") (pinfunction "1_1") (pintype "passive"))
      (node (ref "SUPP_U1") (pin "4") (pinfunction "OUT_4") (pintype "passive"))
    )
    (net (code "30") (name "STACK_CAM_NADIR_3V3") (class "Default")
      (node (ref "SUPP_FB4") (pin "1") (pinfunction "1_1") (pintype "passive"))
    )
    (net (code "31") (name "STACK_CAM_WING_3V3") (class "Default")
      (node (ref "SUPP_FB2") (pin "1") (pinfunction "1_1") (pintype "passive"))
    )
    (net (code "32") (name "STACK_SENS_5V") (class "Default")
      (node (ref "SUPP_FB1") (pin "1") (pinfunction "1_1") (pintype "passive"))
      (node (ref "SUPP_FB3") (pin "1") (pinfunction "1_1") (pintype "passive"))
      (node (ref "SUPP_FB7") (pin "1") (pinfunction "1_1") (pintype "passive"))
      (node (ref "SUPP_FB8") (pin "1") (pinfunction "1_1") (pintype "passive"))
    )
    (net (code "33") (name "STACK_SUNS_3V3") (class "Default")
      (node (ref "SUPP_FB6") (pin "1") (pinfunction "1_1") (pintype "passive"))
    )
    (net (code "34") (name "SunS_3V3") (class "Default")
      (node (ref "SUPP_C19") (pin "1") (pinfunction "1_1") (pintype "passive"))
      (node (ref "SUPP_C20") (pin "1") (pinfunction "1_1") (pintype "passive"))
      (node (ref "SUPP_FB6") (pin "2") (pinfunction "2_2") (pintype "passive"))
    )
    (net (code "35") (name "SunSref_5V") (class "Default")
      (node (ref "SUPP_C23") (pin "2") (pinfunction "2_2") (pintype "passive"))
      (node (ref "SUPP_C7") (pin "1") (pinfunction "1_1") (pintype "passive"))
      (node (ref "SUPP_FB7") (pin "2") (pinfunction "2_2") (pintype "passive"))
    )
  )
)
